# ADC.net
KiCad netlist of a schematic drawn in Altium Designer
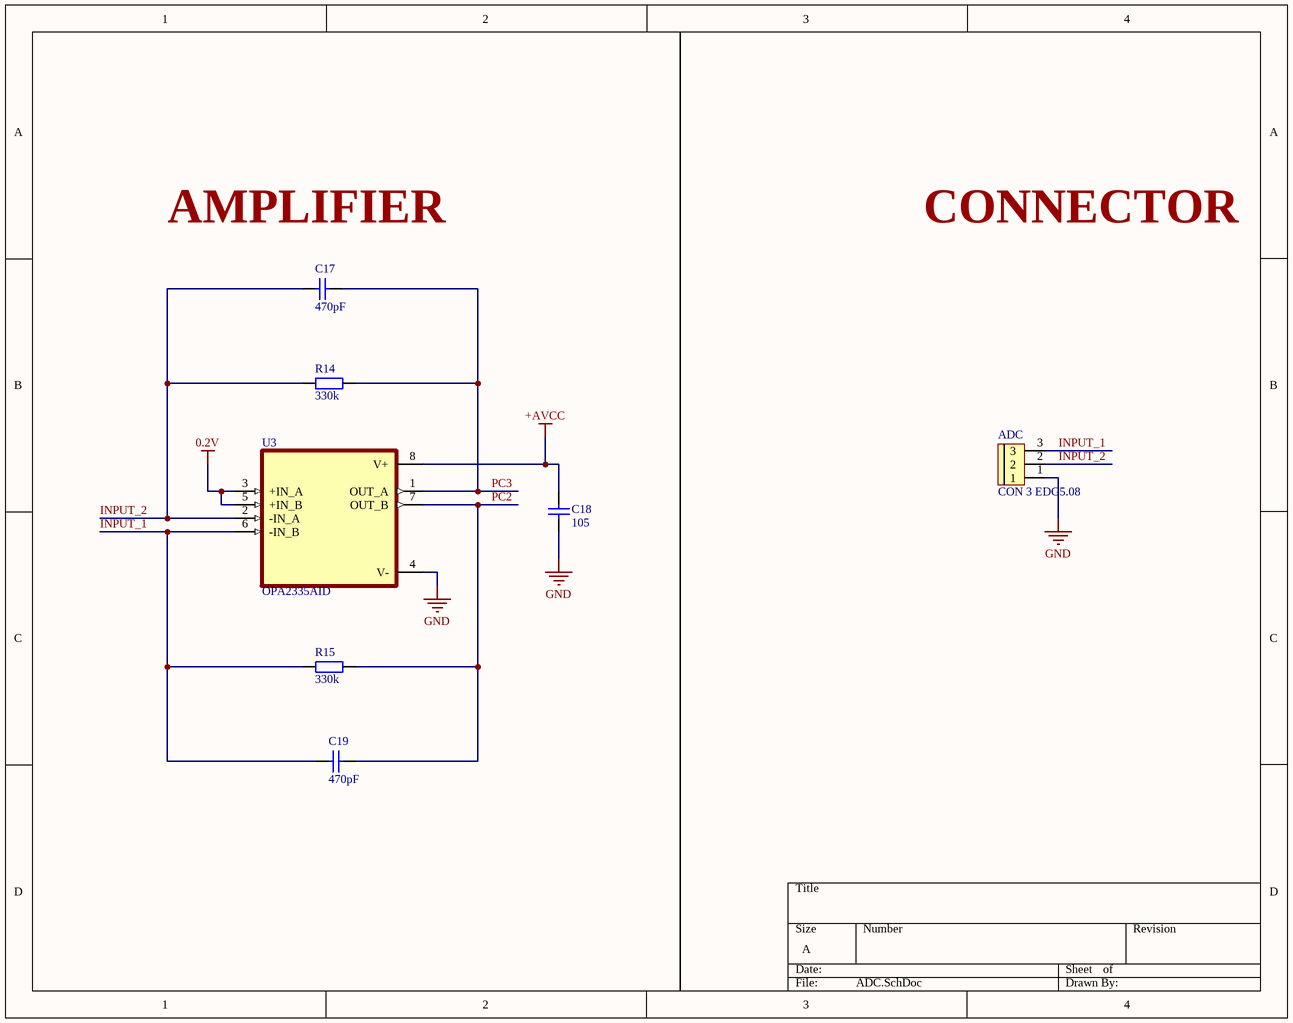
[diagram p0: ADC.SchDoc]

(export (version "E")
  (design (tool "Eeschema 10.0.6"))
  (components
    (comp (ref "ADC")
      (value "CON 3 EDG5.08")
      (footprint "CON 3 3EDG5.08")
      (description "Cắm")
      (libsource (lib "Altium_Lib_by_KhueNguyenCreator") (part "CON 3 EDG5.08"))
    )
    (comp (ref "C17")
      (value "470pF")
      (footprint "tu 0603")
      (description "Dán")
      (libsource (lib "Altium_Lib_by_KhueNguyenCreator") (part "Tu 0603 470pF 50V 10%"))
    )
    (comp (ref "C18")
      (value "105")
      (footprint "tu 1206")
      (description "Dán")
      (libsource (lib "Altium_Lib_by_KhueNguyenCreator") (part "Tu 1206 105 50V 20%"))
    )
    (comp (ref "C19")
      (value "470pF")
      (footprint "tu 0603")
      (description "Dán")
      (libsource (lib "Altium_Lib_by_KhueNguyenCreator") (part "Tu 0603 470pF 50V 10%"))
    )
    (comp (ref "R14")
      (value "330k")
      (footprint "Tro SMD 0805")
      (description "Dán")
      (libsource (lib "Altium_Lib_by_KhueNguyenCreator") (part "Tro 0805 5% 330k"))
    )
    (comp (ref "R15")
      (value "330k")
      (footprint "Tro SMD 0805")
      (description "Dán")
      (libsource (lib "Altium_Lib_by_KhueNguyenCreator") (part "Tro 0805 5% 330k"))
    )
    (comp (ref "U3")
      (value "OPA2335AID")
      (footprint "OPA2335AID:SOIC127P599X175-8N")
      (fields (field (name "MF") "{'manufacturer': u'Texas Instruments'}"))
      (libsource (lib "*") (part "OPA2335AID"))
    )
  )
  (nets
    (net (code "1") (name "+AVCC") (class "Default")
      (node (ref "C18") (pin "1") (pinfunction "1_1") (pintype "passive"))
      (node (ref "U3") (pin "8") (pinfunction "V+_8") (pintype "power_in"))
    )
    (net (code "2") (name "/INPUT_1") (class "Default")
      (node (ref "ADC") (pin "3") (pinfunction "3_3") (pintype "passive"))
      (node (ref "C19") (pin "2") (pinfunction "2_2") (pintype "passive"))
      (node (ref "R15") (pin "1") (pinfunction "1_1") (pintype "passive"))
      (node (ref "U3") (pin "6") (pinfunction "-IN_B_6") (pintype "input"))
    )
    (net (code "3") (name "/INPUT_2") (class "Default")
      (node (ref "ADC") (pin "2") (pinfunction "2_2") (pintype "passive"))
      (node (ref "C17") (pin "2") (pinfunction "2_2") (pintype "passive"))
      (node (ref "R14") (pin "1") (pinfunction "1_1") (pintype "passive"))
      (node (ref "U3") (pin "2") (pinfunction "-IN_A_2") (pintype "input"))
    )
    (net (code "4") (name "/PC2") (class "Default")
      (node (ref "C19") (pin "1") (pinfunction "1_1") (pintype "passive"))
      (node (ref "R15") (pin "2") (pinfunction "2_2") (pintype "passive"))
      (node (ref "U3") (pin "7") (pinfunction "OUT_B_7") (pintype "output"))
    )
    (net (code "5") (name "/PC3") (class "Default")
      (node (ref "C17") (pin "1") (pinfunction "1_1") (pintype "passive"))
      (node (ref "R14") (pin "2") (pinfunction "2_2") (pintype "passive"))
      (node (ref "U3") (pin "1") (pinfunction "OUT_A_1") (pintype "output"))
    )
    (net (code "6") (name "0.2V") (class "Default")
      (node (ref "U3") (pin "3") (pinfunction "+IN_A_3") (pintype "input"))
      (node (ref "U3") (pin "5") (pinfunction "+IN_B_5") (pintype "input"))
    )
    (net (code "7") (name "GND") (class "Default")
      (node (ref "ADC") (pin "1") (pinfunction "1_1") (pintype "passive"))
      (node (ref "C18") (pin "2") (pinfunction "2_2") (pintype "passive"))
      (node (ref "U3") (pin "4") (pinfunction "V-_4") (pintype "power_in"))
    )
  )
)
